# TelecarRemoteControl.net
KiCad netlist of a schematic drawn in Altium Designer
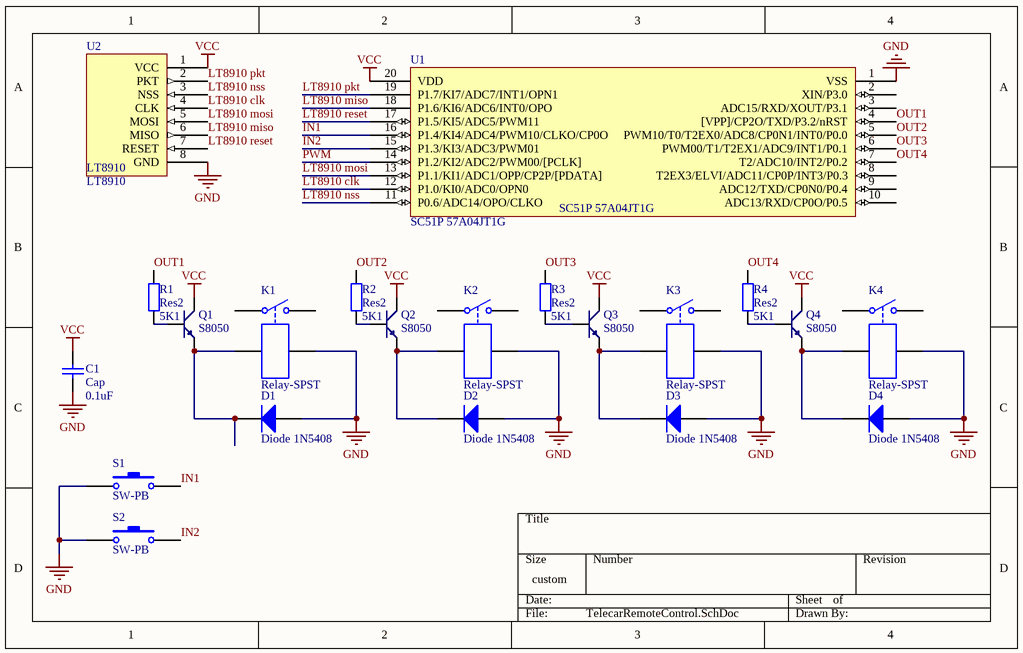
[diagram p0: TelecarRemoteControl.SchDoc]

(export (version "E")
  (design (tool "Eeschema 10.0.6"))
  (components
    (comp (ref "C1")
      (value "Cap")
      (footprint "RAD-0.3")
      (description "Capacitor")
      (fields (field (name "ALTIUM_VALUE") "0.1uF") (field (name "PUBLISHER") "Altium Limited"))
      (libsource (lib "Miscellaneous Devices") (part "Cap"))
    )
    (comp (ref "D1")
      (value "Diode 1N5408")
      (footprint "DIO18.84-9.6x5.6")
      (description "3 Amp Medium Power Silicon Rectifier Diode")
      (fields (field (name "PUBLISHER") "Altium Limited"))
      (libsource (lib "Miscellaneous Devices") (part "Diode 1N5408"))
    )
    (comp (ref "D2")
      (value "Diode 1N5408")
      (footprint "DIO18.84-9.6x5.6")
      (description "3 Amp Medium Power Silicon Rectifier Diode")
      (fields (field (name "PUBLISHER") "Altium Limited"))
      (libsource (lib "Miscellaneous Devices") (part "Diode 1N5408"))
    )
    (comp (ref "D3")
      (value "Diode 1N5408")
      (footprint "DIO18.84-9.6x5.6")
      (description "3 Amp Medium Power Silicon Rectifier Diode")
      (fields (field (name "PUBLISHER") "Altium Limited"))
      (libsource (lib "Miscellaneous Devices") (part "Diode 1N5408"))
    )
    (comp (ref "D4")
      (value "Diode 1N5408")
      (footprint "DIO18.84-9.6x5.6")
      (description "3 Amp Medium Power Silicon Rectifier Diode")
      (fields (field (name "PUBLISHER") "Altium Limited"))
      (libsource (lib "Miscellaneous Devices") (part "Diode 1N5408"))
    )
    (comp (ref "K1")
      (value "Relay-SPST")
      (footprint "DIP-P4")
      (description "Single-Pole Single-Throw Relay")
      (fields (field (name "PUBLISHER") "Altium Limited"))
      (libsource (lib "Miscellaneous Devices") (part "Relay-SPST"))
    )
    (comp (ref "K2")
      (value "Relay-SPST")
      (footprint "DIP-P4")
      (description "Single-Pole Single-Throw Relay")
      (fields (field (name "PUBLISHER") "Altium Limited"))
      (libsource (lib "Miscellaneous Devices") (part "Relay-SPST"))
    )
    (comp (ref "K3")
      (value "Relay-SPST")
      (footprint "DIP-P4")
      (description "Single-Pole Single-Throw Relay")
      (fields (field (name "PUBLISHER") "Altium Limited"))
      (libsource (lib "Miscellaneous Devices") (part "Relay-SPST"))
    )
    (comp (ref "K4")
      (value "Relay-SPST")
      (footprint "DIP-P4")
      (description "Single-Pole Single-Throw Relay")
      (fields (field (name "PUBLISHER") "Altium Limited"))
      (libsource (lib "Miscellaneous Devices") (part "Relay-SPST"))
    )
    (comp (ref "Q1")
      (value "S8050")
      (footprint "SOT-23R")
      (description "8050/BCW846/BCW847")
      (libsource (lib "战舰STM32开发板底板封装库") (part "NPN"))
    )
    (comp (ref "Q2")
      (value "S8050")
      (footprint "SOT-23R")
      (description "8050/BCW846/BCW847")
      (libsource (lib "战舰STM32开发板底板封装库") (part "NPN"))
    )
    (comp (ref "Q3")
      (value "S8050")
      (footprint "SOT-23R")
      (description "8050/BCW846/BCW847")
      (libsource (lib "战舰STM32开发板底板封装库") (part "NPN"))
    )
    (comp (ref "Q4")
      (value "S8050")
      (footprint "SOT-23R")
      (description "8050/BCW846/BCW847")
      (libsource (lib "战舰STM32开发板底板封装库") (part "NPN"))
    )
    (comp (ref "R1")
      (value "Res2")
      (footprint "AXIAL-0.4")
      (description "Resistor")
      (fields (field (name "ALTIUM_VALUE") "5K1") (field (name "PUBLISHER") "Altium Limited"))
      (libsource (lib "Miscellaneous Devices") (part "Res2"))
    )
    (comp (ref "R2")
      (value "Res2")
      (footprint "AXIAL-0.4")
      (description "Resistor")
      (fields (field (name "ALTIUM_VALUE") "5K1") (field (name "PUBLISHER") "Altium Limited"))
      (libsource (lib "Miscellaneous Devices") (part "Res2"))
    )
    (comp (ref "R3")
      (value "Res2")
      (footprint "AXIAL-0.4")
      (description "Resistor")
      (fields (field (name "ALTIUM_VALUE") "5K1") (field (name "PUBLISHER") "Altium Limited"))
      (libsource (lib "Miscellaneous Devices") (part "Res2"))
    )
    (comp (ref "R4")
      (value "Res2")
      (footprint "AXIAL-0.4")
      (description "Resistor")
      (fields (field (name "ALTIUM_VALUE") "5K1") (field (name "PUBLISHER") "Altium Limited"))
      (libsource (lib "Miscellaneous Devices") (part "Res2"))
    )
    (comp (ref "S1")
      (value "SW-PB")
      (footprint "SPST-2")
      (description "Switch")
      (fields (field (name "PUBLISHER") "Altium Limited"))
      (libsource (lib "Miscellaneous Devices") (part "SW-PB"))
    )
    (comp (ref "S2")
      (value "SW-PB")
      (footprint "SPST-2")
      (description "Switch")
      (fields (field (name "PUBLISHER") "Altium Limited"))
      (libsource (lib "Miscellaneous Devices") (part "SW-PB"))
    )
    (comp (ref "U1") (value "SC51P 57A04JT1G") (libsource (lib "glib") (part "SC51P 57A04JT1G")))
    (comp (ref "U2") (value "LT8910") (libsource (lib "glib") (part "LT8910")))
  )
  (nets
    (net (code "1") (name "/IN1") (class "Default")
      (node (ref "S1") (pin "2") (pinfunction "2_2") (pintype "passive"))
      (node (ref "U1") (pin "16") (pinfunction "P1.4/KI4/ADC4/PWM10/CLKO/CP0O_16") (pintype "bidirectional"))
    )
    (net (code "2") (name "/IN2") (class "Default")
      (node (ref "S2") (pin "2") (pinfunction "2_2") (pintype "passive"))
      (node (ref "U1") (pin "15") (pinfunction "P1.3/KI3/ADC3/PWM01_15") (pintype "bidirectional"))
    )
    (net (code "3") (name "/LT8910 clk") (class "Default")
      (node (ref "U1") (pin "12") (pinfunction "P1.0/KI0/ADC0/OPN0_12") (pintype "bidirectional"))
      (node (ref "U2") (pin "4") (pinfunction "CLK_4") (pintype "input"))
    )
    (net (code "4") (name "/LT8910 miso") (class "Default")
      (node (ref "U1") (pin "18") (pinfunction "P1.6/KI6/ADC6/INT0/OPO_18") (pintype "power_in"))
      (node (ref "U2") (pin "6") (pinfunction "MISO_6") (pintype "output"))
    )
    (net (code "5") (name "/LT8910 mosi") (class "Default")
      (node (ref "U1") (pin "13") (pinfunction "P1.1/KI1/ADC1/OPP/CP2P/[PDATA]_13") (pintype "bidirectional"))
      (node (ref "U2") (pin "5") (pinfunction "MOSI_5") (pintype "input"))
    )
    (net (code "6") (name "/LT8910 nss") (class "Default")
      (node (ref "U1") (pin "11") (pinfunction "P0.6/ADC14/OPO/CLKO_11") (pintype "bidirectional"))
      (node (ref "U2") (pin "3") (pinfunction "NSS_3") (pintype "input"))
    )
    (net (code "7") (name "/LT8910 pkt") (class "Default")
      (node (ref "U1") (pin "19") (pinfunction "P1.7/KI7/ADC7/INT1/OPN1_19") (pintype "power_in"))
      (node (ref "U2") (pin "2") (pinfunction "PKT_2") (pintype "output"))
    )
    (net (code "8") (name "/LT8910 reset") (class "Default")
      (node (ref "U1") (pin "17") (pinfunction "P1.5/KI5/ADC5/PWM11_17") (pintype "bidirectional"))
      (node (ref "U2") (pin "7") (pinfunction "RESET_7") (pintype "input"))
    )
    (net (code "9") (name "/OUT1") (class "Default")
      (node (ref "R1") (pin "2") (pinfunction "2_2") (pintype "passive"))
      (node (ref "U1") (pin "4") (pinfunction "[VPP]/CP2O/TXD/P3.2/nRST_4") (pintype "bidirectional"))
    )
    (net (code "10") (name "/OUT2") (class "Default")
      (node (ref "R2") (pin "2") (pinfunction "2_2") (pintype "passive"))
      (node (ref "U1") (pin "5") (pinfunction "PWM10/T0/T2EX0/ADC8/CP0N1/INT0/P0.0_5") (pintype "bidirectional"))
    )
    (net (code "11") (name "/OUT3") (class "Default")
      (node (ref "R3") (pin "2") (pinfunction "2_2") (pintype "passive"))
      (node (ref "U1") (pin "6") (pinfunction "PWM00/T1/T2EX1/ADC9/INT1/P0.1_6") (pintype "bidirectional"))
    )
    (net (code "12") (name "/OUT4") (class "Default")
      (node (ref "R4") (pin "2") (pinfunction "2_2") (pintype "passive"))
      (node (ref "U1") (pin "7") (pinfunction "T2/ADC10/INT2/P0.2_7") (pintype "bidirectional"))
    )
    (net (code "13") (name "/PWM") (class "Default")
      (node (ref "U1") (pin "14") (pinfunction "P1.2/KI2/ADC2/PWM00/[PCLK]_14") (pintype "bidirectional"))
    )
    (net (code "14") (name "GND") (class "Default")
      (node (ref "C1") (pin "1") (pinfunction "1_1") (pintype "passive"))
      (node (ref "D1") (pin "1") (pinfunction "A_1") (pintype "passive"))
      (node (ref "D2") (pin "1") (pinfunction "A_1") (pintype "passive"))
      (node (ref "D3") (pin "1") (pinfunction "A_1") (pintype "passive"))
      (node (ref "D4") (pin "1") (pinfunction "A_1") (pintype "passive"))
      (node (ref "K1") (pin "4") (pinfunction "4_4") (pintype "passive"))
      (node (ref "K2") (pin "4") (pinfunction "4_4") (pintype "passive"))
      (node (ref "K3") (pin "4") (pinfunction "4_4") (pintype "passive"))
      (node (ref "K4") (pin "4") (pinfunction "4_4") (pintype "passive"))
      (node (ref "S1") (pin "1") (pinfunction "1_1") (pintype "passive"))
      (node (ref "S2") (pin "1") (pinfunction "1_1") (pintype "passive"))
      (node (ref "U1") (pin "1") (pinfunction "VSS_1") (pintype "power_in"))
      (node (ref "U2") (pin "8") (pinfunction "GND_8") (pintype "power_in"))
    )
    (net (code "15") (name "Net-(D1-K)") (class "Default")
      (node (ref "D1") (pin "2") (pinfunction "K_2") (pintype "passive"))
      (node (ref "K1") (pin "3") (pinfunction "3_3") (pintype "passive"))
      (node (ref "Q1") (pin "1") (pinfunction "E_1") (pintype "passive"))
    )
    (net (code "16") (name "Net-(D2-K)") (class "Default")
      (node (ref "D2") (pin "2") (pinfunction "K_2") (pintype "passive"))
      (node (ref "K2") (pin "3") (pinfunction "3_3") (pintype "passive"))
      (node (ref "Q2") (pin "1") (pinfunction "E_1") (pintype "passive"))
    )
    (net (code "17") (name "Net-(D3-K)") (class "Default")
      (node (ref "D3") (pin "2") (pinfunction "K_2") (pintype "passive"))
      (node (ref "K3") (pin "3") (pinfunction "3_3") (pintype "passive"))
      (node (ref "Q3") (pin "1") (pinfunction "E_1") (pintype "passive"))
    )
    (net (code "18") (name "Net-(D4-K)") (class "Default")
      (node (ref "D4") (pin "2") (pinfunction "K_2") (pintype "passive"))
      (node (ref "K4") (pin "3") (pinfunction "3_3") (pintype "passive"))
      (node (ref "Q4") (pin "1") (pinfunction "E_1") (pintype "passive"))
    )
    (net (code "19") (name "Net-(Q1-B)") (class "Default")
      (node (ref "Q1") (pin "2") (pinfunction "B_2") (pintype "passive"))
      (node (ref "R1") (pin "1") (pinfunction "1_1") (pintype "passive"))
    )
    (net (code "20") (name "Net-(Q2-B)") (class "Default")
      (node (ref "Q2") (pin "2") (pinfunction "B_2") (pintype "passive"))
      (node (ref "R2") (pin "1") (pinfunction "1_1") (pintype "passive"))
    )
    (net (code "21") (name "Net-(Q3-B)") (class "Default")
      (node (ref "Q3") (pin "2") (pinfunction "B_2") (pintype "passive"))
      (node (ref "R3") (pin "1") (pinfunction "1_1") (pintype "passive"))
    )
    (net (code "22") (name "Net-(Q4-B)") (class "Default")
      (node (ref "Q4") (pin "2") (pinfunction "B_2") (pintype "passive"))
      (node (ref "R4") (pin "1") (pinfunction "1_1") (pintype "passive"))
    )
    (net (code "23") (name "VCC") (class "Default")
      (node (ref "C1") (pin "2") (pinfunction "2_2") (pintype "passive"))
      (node (ref "Q1") (pin "3") (pinfunction "C_3") (pintype "passive"))
      (node (ref "Q2") (pin "3") (pinfunction "C_3") (pintype "passive"))
      (node (ref "Q3") (pin "3") (pinfunction "C_3") (pintype "passive"))
      (node (ref "Q4") (pin "3") (pinfunction "C_3") (pintype "passive"))
      (node (ref "U1") (pin "20") (pinfunction "VDD_20") (pintype "power_in"))
      (node (ref "U2") (pin "1") (pinfunction "VCC_1") (pintype "power_in"))
    )
    (net (code "24") (name "unconnected-(K1-Pad1)") (class "Default")
      (node (ref "K1") (pin "1") (pinfunction "1_1") (pintype "passive"))
    )
    (net (code "25") (name "unconnected-(K1-Pad2)") (class "Default")
      (node (ref "K1") (pin "2") (pinfunction "2_2") (pintype "passive"))
    )
    (net (code "26") (name "unconnected-(K2-Pad1)") (class "Default")
      (node (ref "K2") (pin "1") (pinfunction "1_1") (pintype "passive"))
    )
    (net (code "27") (name "unconnected-(K2-Pad2)") (class "Default")
      (node (ref "K2") (pin "2") (pinfunction "2_2") (pintype "passive"))
    )
    (net (code "28") (name "unconnected-(K3-Pad1)") (class "Default")
      (node (ref "K3") (pin "1") (pinfunction "1_1") (pintype "passive"))
    )
    (net (code "29") (name "unconnected-(K3-Pad2)") (class "Default")
      (node (ref "K3") (pin "2") (pinfunction "2_2") (pintype "passive"))
    )
    (net (code "30") (name "unconnected-(K4-Pad1)") (class "Default")
      (node (ref "K4") (pin "1") (pinfunction "1_1") (pintype "passive"))
    )
    (net (code "31") (name "unconnected-(K4-Pad2)") (class "Default")
      (node (ref "K4") (pin "2") (pinfunction "2_2") (pintype "passive"))
    )
    (net (code "32") (name "unconnected-(U1-ADC12{slash}TXD{slash}CP0N0{slash}P0.4-Pad9)") (class "Default")
      (node (ref "U1") (pin "9") (pinfunction "ADC12/TXD/CP0N0/P0.4_9") (pintype "bidirectional"))
    )
    (net (code "33") (name "unconnected-(U1-ADC13{slash}RXD{slash}CP0O{slash}P0.5-Pad10)") (class "Default")
      (node (ref "U1") (pin "10") (pinfunction "ADC13/RXD/CP0O/P0.5_10") (pintype "bidirectional"))
    )
    (net (code "34") (name "unconnected-(U1-ADC15{slash}RXD{slash}XOUT{slash}P3.1-Pad3)") (class "Default")
      (node (ref "U1") (pin "3") (pinfunction "ADC15/RXD/XOUT/P3.1_3") (pintype "bidirectional"))
    )
    (net (code "35") (name "unconnected-(U1-T2EX3{slash}ELVI{slash}ADC11{slash}CP0P{slash}INT3{slash}P0.3-Pad8)") (class "Default")
      (node (ref "U1") (pin "8") (pinfunction "T2EX3/ELVI/ADC11/CP0P/INT3/P0.3_8") (pintype "bidirectional"))
    )
    (net (code "36") (name "unconnected-(U1-XIN{slash}P3.0-Pad2)") (class "Default")
      (node (ref "U1") (pin "2") (pinfunction "XIN/P3.0_2") (pintype "bidirectional"))
    )
  )
)
